# carrier.net
KiCad netlist of a schematic drawn in EAGLE
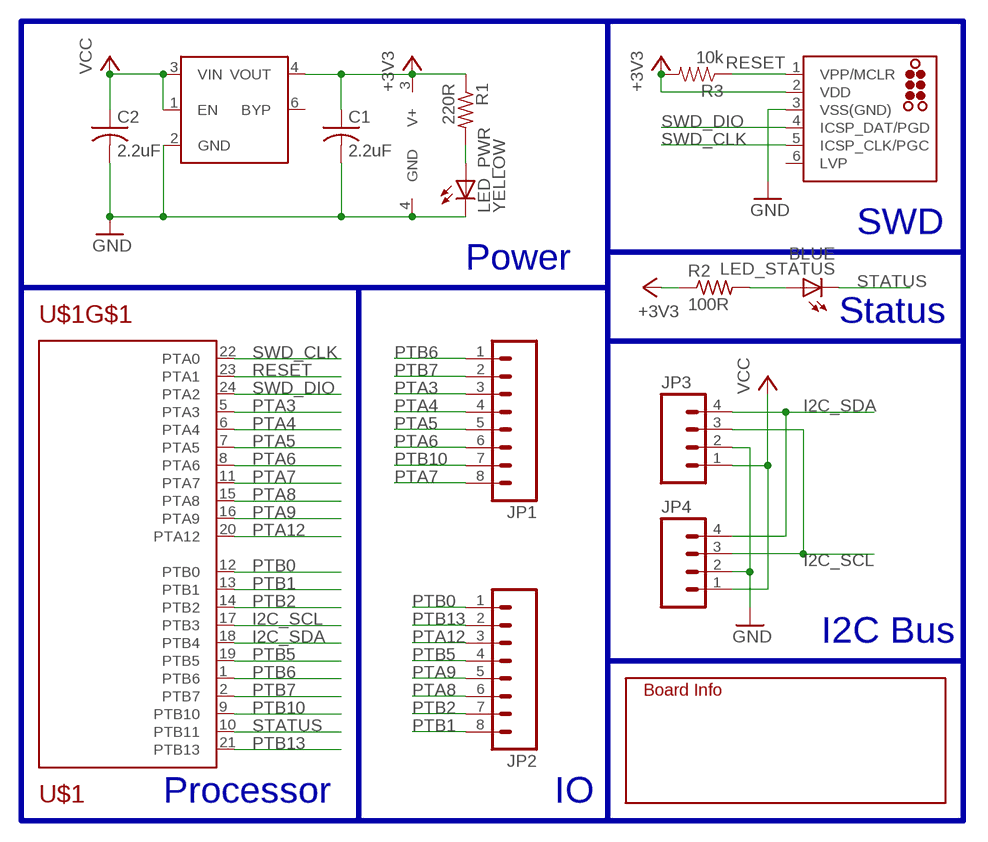
[diagram p0: schematic, sheet 1]

(export (version "E")
  (design (tool "Eeschema 10.0.6"))
  (components
    (comp (ref "C1")
      (value "2.2uF")
      (footprint "eagle-import:C0402")
      (libsource (lib "eagle-import") (part "C-USC0402"))
    )
    (comp (ref "C2")
      (value "2.2uF")
      (footprint "eagle-import:C0402")
      (libsource (lib "eagle-import") (part "C-USC0402"))
    )
    (comp (ref "J1")
      (value "TC2030-MCP-NL")
      (footprint "eagle-import:TC2030-MCP-NL")
      (libsource (lib "eagle-import") (part "TC2030-MCP-NL"))
    )
    (comp (ref "JP1")
      (value "M081X08")
      (footprint "eagle-import:1X08")
      (libsource (lib "eagle-import") (part "M081X08"))
    )
    (comp (ref "JP2")
      (value "M081X08")
      (footprint "eagle-import:1X08")
      (libsource (lib "eagle-import") (part "M081X08"))
    )
    (comp (ref "JP3")
      (value "M04PTH")
      (footprint "eagle-import:1X04")
      (libsource (lib "eagle-import") (part "M04PTH"))
    )
    (comp (ref "JP4")
      (value "M04PTH")
      (footprint "eagle-import:1X04")
      (libsource (lib "eagle-import") (part "M04PTH"))
    )
    (comp (ref "LED_PWR")
      (value "YELLOW")
      (footprint "eagle-import:SML0603")
      (libsource (lib "eagle-import") (part "LEDSML0603"))
    )
    (comp (ref "LED_STATUS")
      (value "BLUE")
      (footprint "eagle-import:SML0603")
      (libsource (lib "eagle-import") (part "LEDSML0603"))
    )
    (comp (ref "R1")
      (value "220R")
      (footprint "eagle-import:R0402")
      (libsource (lib "eagle-import") (part "R-US_R0402"))
    )
    (comp (ref "R2")
      (value "100R")
      (footprint "eagle-import:R0402")
      (libsource (lib "eagle-import") (part "R-US_R0402"))
    )
    (comp (ref "R3")
      (value "10k")
      (footprint "eagle-import:0402-RES")
      (libsource (lib "eagle-import") (part "RESISTOR0402-RES"))
    )
    (comp (ref "U$1")
      (value "MKL05Z32VFK4-QFN")
      (footprint "eagle-import:QFN-24")
      (libsource (lib "eagle-import") (part "MKL05Z32VFK4-QFN"))
    )
    (comp (ref "U$2")
      (value "MIC5305-MLF")
      (footprint "eagle-import:MLF-6")
      (libsource (lib "eagle-import") (part "MIC5305-MLF"))
    )
    (comp (ref "U$3")
      (value "INFO")
      (footprint "eagle-import:INFO")
      (fields
        (field (name "AUTHOR") "abuchan@berkeley.edu")
        (field (name "DATE") "2015_07_14")
        (field (name "DESIGN") "MODROB_CARRIER")
        (field (name "ORGANIZATION") "UC Berkely ASPIRE")
        (field (name "REVISION") "r0.0")
      )
      (libsource (lib "eagle-import") (part "INFO"))
    )
  )
  (nets
    (net (code "1") (name "+3V3") (class "Default")
      (node (ref "C1") (pin "1") (pinfunction "1_1") (pintype "passive"))
      (node (ref "J1") (pin "2") (pinfunction "VDD_2") (pintype "power_in"))
      (node (ref "R1") (pin "1") (pinfunction "1_1") (pintype "passive"))
      (node (ref "R2") (pin "1") (pinfunction "1_1") (pintype "passive"))
      (node (ref "R3") (pin "2") (pinfunction "2_2") (pintype "passive"))
      (node (ref "U$1") (pin "3") (pinfunction "V+_3") (pintype "power_in"))
      (node (ref "U$2") (pin "4") (pinfunction "VOUT_4") (pintype "bidirectional"))
    )
    (net (code "2") (name "/I2C_SCL") (class "Default")
      (node (ref "JP3") (pin "3") (pinfunction "3_3") (pintype "passive"))
      (node (ref "JP4") (pin "3") (pinfunction "3_3") (pintype "passive"))
      (node (ref "U$1") (pin "17") (pinfunction "PTB3_17") (pintype "bidirectional"))
    )
    (net (code "3") (name "/I2C_SDA") (class "Default")
      (node (ref "JP3") (pin "4") (pinfunction "4_4") (pintype "passive"))
      (node (ref "JP4") (pin "4") (pinfunction "4_4") (pintype "passive"))
      (node (ref "U$1") (pin "18") (pinfunction "PTB4_18") (pintype "bidirectional"))
    )
    (net (code "4") (name "/PTA3") (class "Default")
      (node (ref "JP1") (pin "3") (pinfunction "3_3") (pintype "passive"))
      (node (ref "U$1") (pin "5") (pinfunction "PTA3_5") (pintype "bidirectional"))
    )
    (net (code "5") (name "/PTA4") (class "Default")
      (node (ref "JP1") (pin "4") (pinfunction "4_4") (pintype "passive"))
      (node (ref "U$1") (pin "6") (pinfunction "PTA4_6") (pintype "bidirectional"))
    )
    (net (code "6") (name "/PTA5") (class "Default")
      (node (ref "JP1") (pin "5") (pinfunction "5_5") (pintype "passive"))
      (node (ref "U$1") (pin "7") (pinfunction "PTA5_7") (pintype "bidirectional"))
    )
    (net (code "7") (name "/PTA6") (class "Default")
      (node (ref "JP1") (pin "6") (pinfunction "6_6") (pintype "passive"))
      (node (ref "U$1") (pin "8") (pinfunction "PTA6_8") (pintype "bidirectional"))
    )
    (net (code "8") (name "/PTA7") (class "Default")
      (node (ref "JP1") (pin "8") (pinfunction "8_8") (pintype "passive"))
      (node (ref "U$1") (pin "11") (pinfunction "PTA7_11") (pintype "bidirectional"))
    )
    (net (code "9") (name "/PTA8") (class "Default")
      (node (ref "JP2") (pin "6") (pinfunction "6_6") (pintype "passive"))
      (node (ref "U$1") (pin "15") (pinfunction "PTA8_15") (pintype "bidirectional"))
    )
    (net (code "10") (name "/PTA9") (class "Default")
      (node (ref "JP2") (pin "5") (pinfunction "5_5") (pintype "passive"))
      (node (ref "U$1") (pin "16") (pinfunction "PTA9_16") (pintype "bidirectional"))
    )
    (net (code "11") (name "/PTA12") (class "Default")
      (node (ref "JP2") (pin "3") (pinfunction "3_3") (pintype "passive"))
      (node (ref "U$1") (pin "20") (pinfunction "PTA12_20") (pintype "bidirectional"))
    )
    (net (code "12") (name "/PTB0") (class "Default")
      (node (ref "JP2") (pin "1") (pinfunction "1_1") (pintype "passive"))
      (node (ref "U$1") (pin "12") (pinfunction "PTB0_12") (pintype "bidirectional"))
    )
    (net (code "13") (name "/PTB1") (class "Default")
      (node (ref "JP2") (pin "8") (pinfunction "8_8") (pintype "passive"))
      (node (ref "U$1") (pin "13") (pinfunction "PTB1_13") (pintype "bidirectional"))
    )
    (net (code "14") (name "/PTB2") (class "Default")
      (node (ref "JP2") (pin "7") (pinfunction "7_7") (pintype "passive"))
      (node (ref "U$1") (pin "14") (pinfunction "PTB2_14") (pintype "bidirectional"))
    )
    (net (code "15") (name "/PTB5") (class "Default")
      (node (ref "JP2") (pin "4") (pinfunction "4_4") (pintype "passive"))
      (node (ref "U$1") (pin "19") (pinfunction "PTB5_19") (pintype "bidirectional"))
    )
    (net (code "16") (name "/PTB6") (class "Default")
      (node (ref "JP1") (pin "1") (pinfunction "1_1") (pintype "passive"))
      (node (ref "U$1") (pin "1") (pinfunction "PTB6_1") (pintype "bidirectional"))
    )
    (net (code "17") (name "/PTB7") (class "Default")
      (node (ref "JP1") (pin "2") (pinfunction "2_2") (pintype "passive"))
      (node (ref "U$1") (pin "2") (pinfunction "PTB7_2") (pintype "bidirectional"))
    )
    (net (code "18") (name "/PTB10") (class "Default")
      (node (ref "JP1") (pin "7") (pinfunction "7_7") (pintype "passive"))
      (node (ref "U$1") (pin "9") (pinfunction "PTB10_9") (pintype "bidirectional"))
    )
    (net (code "19") (name "/PTB13") (class "Default")
      (node (ref "JP2") (pin "2") (pinfunction "2_2") (pintype "passive"))
      (node (ref "U$1") (pin "21") (pinfunction "PTB13_21") (pintype "bidirectional"))
    )
    (net (code "20") (name "/RESET") (class "Default")
      (node (ref "J1") (pin "1") (pinfunction "VPP/MCLR_1") (pintype "passive"))
      (node (ref "R3") (pin "1") (pinfunction "1_1") (pintype "passive"))
      (node (ref "U$1") (pin "23") (pinfunction "PTA1_23") (pintype "bidirectional"))
    )
    (net (code "21") (name "/STATUS") (class "Default")
      (node (ref "LED_STATUS") (pin "C") (pinfunction "C_C") (pintype "passive"))
      (node (ref "U$1") (pin "10") (pinfunction "PTB11_10") (pintype "bidirectional"))
    )
    (net (code "22") (name "/SWD_CLK") (class "Default")
      (node (ref "J1") (pin "5") (pinfunction "ICSP_CLK/PGC_5") (pintype "output"))
      (node (ref "U$1") (pin "22") (pinfunction "PTA0_22") (pintype "bidirectional"))
    )
    (net (code "23") (name "/SWD_DIO") (class "Default")
      (node (ref "J1") (pin "4") (pinfunction "ICSP_DAT/PGD_4") (pintype "bidirectional"))
      (node (ref "U$1") (pin "24") (pinfunction "PTA2_24") (pintype "bidirectional"))
    )
    (net (code "24") (name "GND") (class "Default")
      (node (ref "C1") (pin "2") (pinfunction "2_2") (pintype "passive"))
      (node (ref "C2") (pin "2") (pinfunction "2_2") (pintype "passive"))
      (node (ref "J1") (pin "3") (pinfunction "VSS(GND)_3") (pintype "power_in"))
      (node (ref "JP3") (pin "2") (pinfunction "2_2") (pintype "passive"))
      (node (ref "JP4") (pin "2") (pinfunction "2_2") (pintype "passive"))
      (node (ref "LED_PWR") (pin "C") (pinfunction "C_C") (pintype "passive"))
      (node (ref "U$1") (pin "4") (pinfunction "GND_4") (pintype "power_in"))
      (node (ref "U$2") (pin "2") (pinfunction "GND_2") (pintype "bidirectional"))
    )
    (net (code "25") (name "Net-(LED_PWR-PadA)") (class "Default")
      (node (ref "LED_PWR") (pin "A") (pinfunction "A_A") (pintype "passive"))
      (node (ref "R1") (pin "2") (pinfunction "2_2") (pintype "passive"))
    )
    (net (code "26") (name "Net-(LED_STATUS-PadA)") (class "Default")
      (node (ref "LED_STATUS") (pin "A") (pinfunction "A_A") (pintype "passive"))
      (node (ref "R2") (pin "2") (pinfunction "2_2") (pintype "passive"))
    )
    (net (code "27") (name "VCC") (class "Default")
      (node (ref "C2") (pin "1") (pinfunction "1_1") (pintype "passive"))
      (node (ref "JP3") (pin "1") (pinfunction "1_1") (pintype "passive"))
      (node (ref "JP4") (pin "1") (pinfunction "1_1") (pintype "passive"))
      (node (ref "U$2") (pin "1") (pinfunction "EN_1") (pintype "bidirectional"))
      (node (ref "U$2") (pin "3") (pinfunction "VIN_3") (pintype "bidirectional"))
    )
    (net (code "28") (name "unconnected-(J1-LVP-Pad6)") (class "Default")
      (node (ref "J1") (pin "6") (pinfunction "LVP_6") (pintype "bidirectional"))
    )
    (net (code "29") (name "unconnected-(U$2-BYP-Pad6)") (class "Default")
      (node (ref "U$2") (pin "6") (pinfunction "BYP_6") (pintype "bidirectional"))
    )
  )
)
